# R203D.net
KiCad netlist of a schematic drawn in EAGLE
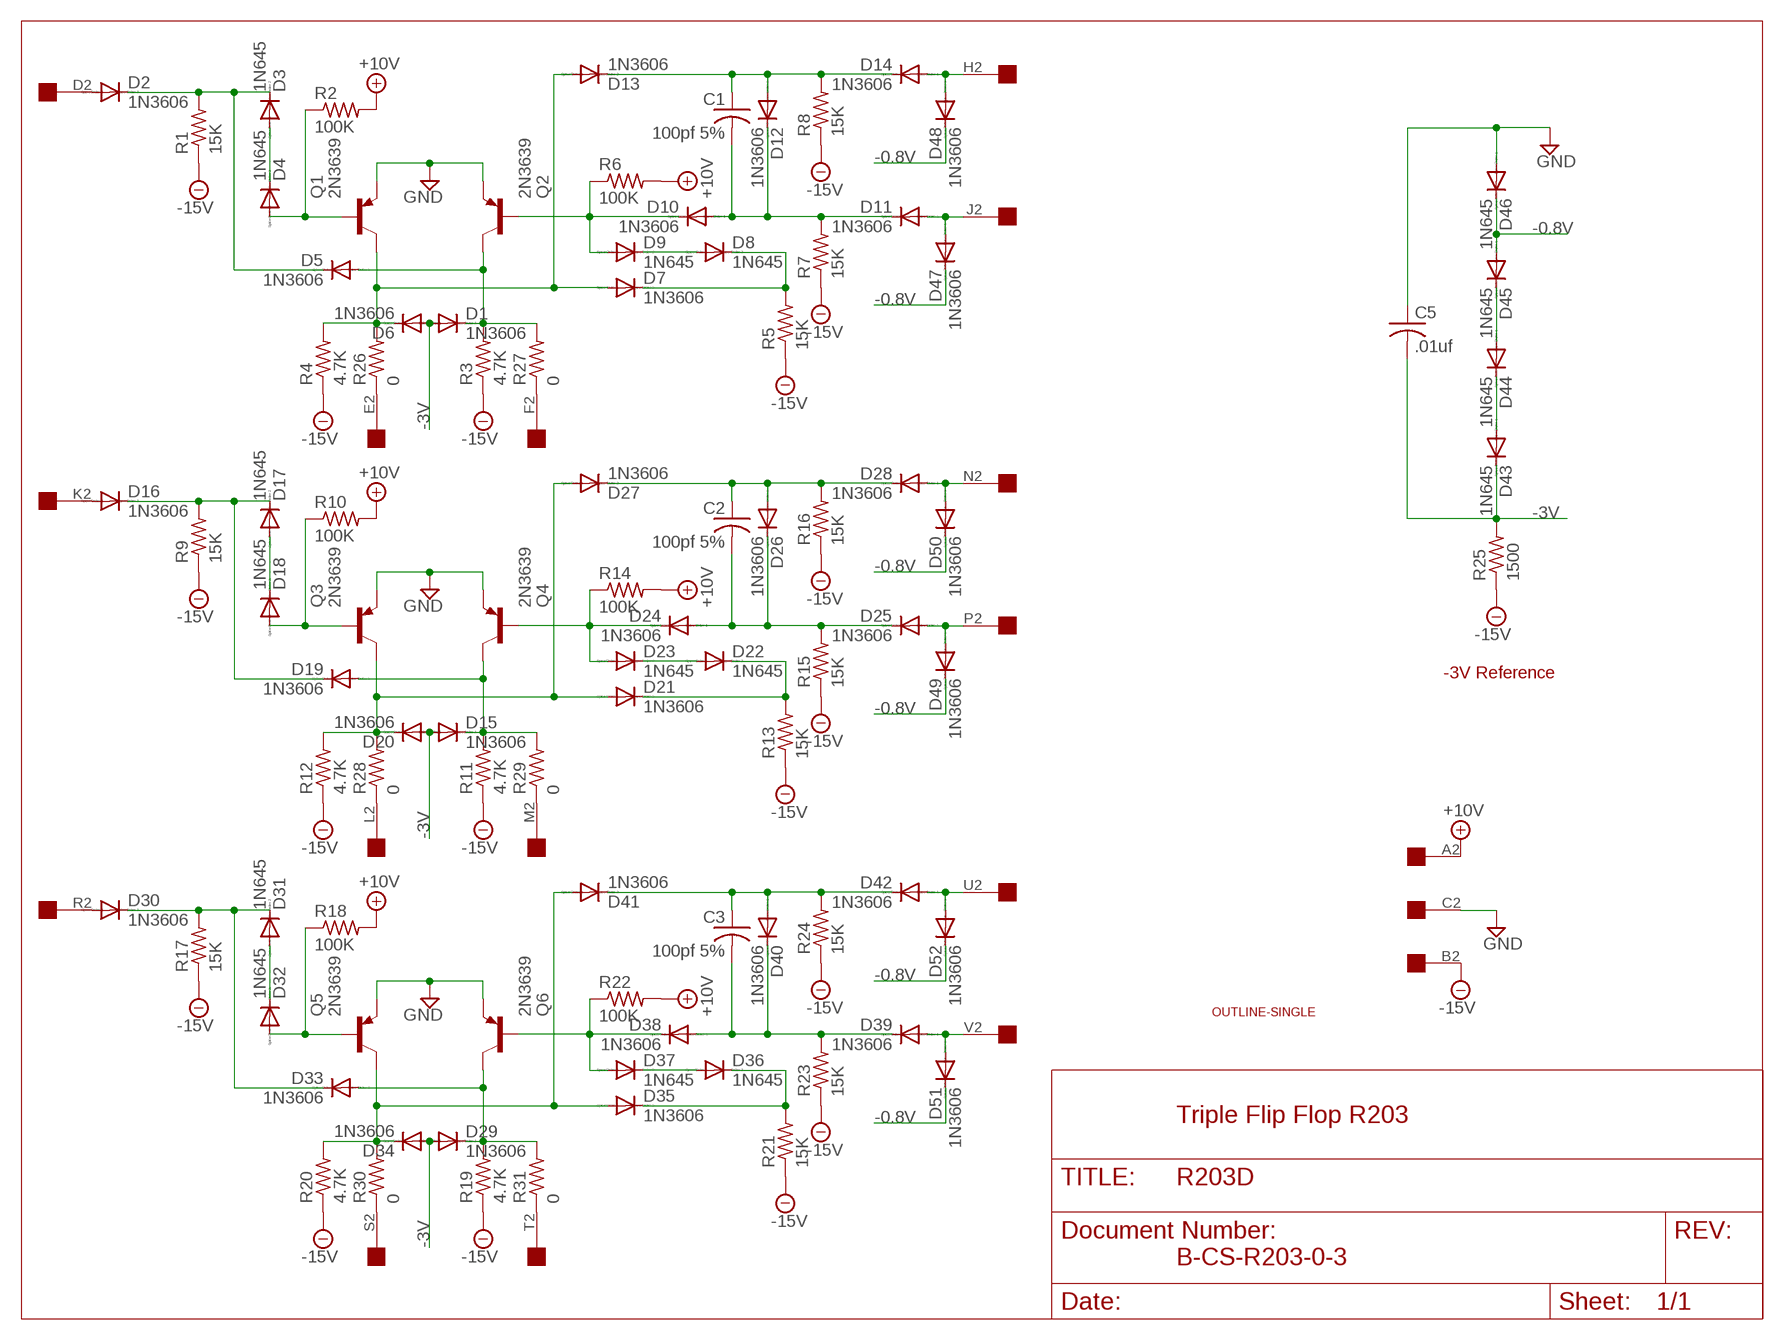
[diagram p0: schematic, sheet 1]

(export (version "E")
  (design (tool "Eeschema 10.0.6"))
  (components
    (comp (ref "C1")
      (value "100pf 5%")
      (footprint "eagle-import:C050-025X075")
      (libsource (lib "eagle-import") (part "C-US050-025X075"))
    )
    (comp (ref "C2")
      (value "100pf 5%")
      (footprint "eagle-import:C050-025X075")
      (libsource (lib "eagle-import") (part "C-US050-025X075"))
    )
    (comp (ref "C3")
      (value "100pf 5%")
      (footprint "eagle-import:C050-025X075")
      (libsource (lib "eagle-import") (part "C-US050-025X075"))
    )
    (comp (ref "C5")
      (value ".01uf")
      (footprint "eagle-import:C050-025X075")
      (libsource (lib "eagle-import") (part "C-US050-025X075"))
    )
    (comp (ref "D1")
      (value "1N3606")
      (footprint "eagle-import:DO35-10")
      (libsource (lib "eagle-import") (part "1N4148DO35-10"))
    )
    (comp (ref "D2")
      (value "1N3606")
      (footprint "eagle-import:DO35-10")
      (libsource (lib "eagle-import") (part "1N4148DO35-10"))
    )
    (comp (ref "D3")
      (value "1N645")
      (footprint "eagle-import:DO35-10")
      (libsource (lib "eagle-import") (part "1N4148DO35-10"))
    )
    (comp (ref "D4")
      (value "1N645")
      (footprint "eagle-import:DO35-10")
      (libsource (lib "eagle-import") (part "1N4148DO35-10"))
    )
    (comp (ref "D5")
      (value "1N3606")
      (footprint "eagle-import:DO35-10")
      (libsource (lib "eagle-import") (part "1N4148DO35-10"))
    )
    (comp (ref "D6")
      (value "1N3606")
      (footprint "eagle-import:DO35-10")
      (libsource (lib "eagle-import") (part "1N4148DO35-10"))
    )
    (comp (ref "D7")
      (value "1N3606")
      (footprint "eagle-import:DO35-10")
      (libsource (lib "eagle-import") (part "1N4148DO35-10"))
    )
    (comp (ref "D8")
      (value "1N645")
      (footprint "eagle-import:DO35-10")
      (libsource (lib "eagle-import") (part "1N4148DO35-10"))
    )
    (comp (ref "D9")
      (value "1N645")
      (footprint "eagle-import:DO35-10")
      (libsource (lib "eagle-import") (part "1N4148DO35-10"))
    )
    (comp (ref "D10")
      (value "1N3606")
      (footprint "eagle-import:DO35-10")
      (libsource (lib "eagle-import") (part "1N4148DO35-10"))
    )
    (comp (ref "D11")
      (value "1N3606")
      (footprint "eagle-import:DO35-10")
      (libsource (lib "eagle-import") (part "1N4148DO35-10"))
    )
    (comp (ref "D12")
      (value "1N3606")
      (footprint "eagle-import:DO35-10")
      (libsource (lib "eagle-import") (part "1N4148DO35-10"))
    )
    (comp (ref "D13")
      (value "1N3606")
      (footprint "eagle-import:DO35-10")
      (libsource (lib "eagle-import") (part "1N4148DO35-10"))
    )
    (comp (ref "D14")
      (value "1N3606")
      (footprint "eagle-import:DO35-10")
      (libsource (lib "eagle-import") (part "1N4148DO35-10"))
    )
    (comp (ref "D15")
      (value "1N3606")
      (footprint "eagle-import:DO35-10")
      (libsource (lib "eagle-import") (part "1N4148DO35-10"))
    )
    (comp (ref "D16")
      (value "1N3606")
      (footprint "eagle-import:DO35-10")
      (libsource (lib "eagle-import") (part "1N4148DO35-10"))
    )
    (comp (ref "D17")
      (value "1N645")
      (footprint "eagle-import:DO35-10")
      (libsource (lib "eagle-import") (part "1N4148DO35-10"))
    )
    (comp (ref "D18")
      (value "1N645")
      (footprint "eagle-import:DO35-10")
      (libsource (lib "eagle-import") (part "1N4148DO35-10"))
    )
    (comp (ref "D19")
      (value "1N3606")
      (footprint "eagle-import:DO35-10")
      (libsource (lib "eagle-import") (part "1N4148DO35-10"))
    )
    (comp (ref "D20")
      (value "1N3606")
      (footprint "eagle-import:DO35-10")
      (libsource (lib "eagle-import") (part "1N4148DO35-10"))
    )
    (comp (ref "D21")
      (value "1N3606")
      (footprint "eagle-import:DO35-10")
      (libsource (lib "eagle-import") (part "1N4148DO35-10"))
    )
    (comp (ref "D22")
      (value "1N645")
      (footprint "eagle-import:DO35-10")
      (libsource (lib "eagle-import") (part "1N4148DO35-10"))
    )
    (comp (ref "D23")
      (value "1N645")
      (footprint "eagle-import:DO35-10")
      (libsource (lib "eagle-import") (part "1N4148DO35-10"))
    )
    (comp (ref "D24")
      (value "1N3606")
      (footprint "eagle-import:DO35-10")
      (libsource (lib "eagle-import") (part "1N4148DO35-10"))
    )
    (comp (ref "D25")
      (value "1N3606")
      (footprint "eagle-import:DO35-10")
      (libsource (lib "eagle-import") (part "1N4148DO35-10"))
    )
    (comp (ref "D26")
      (value "1N3606")
      (footprint "eagle-import:DO35-10")
      (libsource (lib "eagle-import") (part "1N4148DO35-10"))
    )
    (comp (ref "D27")
      (value "1N3606")
      (footprint "eagle-import:DO35-10")
      (libsource (lib "eagle-import") (part "1N4148DO35-10"))
    )
    (comp (ref "D28")
      (value "1N3606")
      (footprint "eagle-import:DO35-10")
      (libsource (lib "eagle-import") (part "1N4148DO35-10"))
    )
    (comp (ref "D29")
      (value "1N3606")
      (footprint "eagle-import:DO35-10")
      (libsource (lib "eagle-import") (part "1N4148DO35-10"))
    )
    (comp (ref "D30")
      (value "1N3606")
      (footprint "eagle-import:DO35-10")
      (libsource (lib "eagle-import") (part "1N4148DO35-10"))
    )
    (comp (ref "D31")
      (value "1N645")
      (footprint "eagle-import:DO35-10")
      (libsource (lib "eagle-import") (part "1N4148DO35-10"))
    )
    (comp (ref "D32")
      (value "1N645")
      (footprint "eagle-import:DO35-10")
      (libsource (lib "eagle-import") (part "1N4148DO35-10"))
    )
    (comp (ref "D33")
      (value "1N3606")
      (footprint "eagle-import:DO35-10")
      (libsource (lib "eagle-import") (part "1N4148DO35-10"))
    )
    (comp (ref "D34")
      (value "1N3606")
      (footprint "eagle-import:DO35-10")
      (libsource (lib "eagle-import") (part "1N4148DO35-10"))
    )
    (comp (ref "D35")
      (value "1N3606")
      (footprint "eagle-import:DO35-10")
      (libsource (lib "eagle-import") (part "1N4148DO35-10"))
    )
    (comp (ref "D36")
      (value "1N645")
      (footprint "eagle-import:DO35-10")
      (libsource (lib "eagle-import") (part "1N4148DO35-10"))
    )
    (comp (ref "D37")
      (value "1N645")
      (footprint "eagle-import:DO35-10")
      (libsource (lib "eagle-import") (part "1N4148DO35-10"))
    )
    (comp (ref "D38")
      (value "1N3606")
      (footprint "eagle-import:DO35-10")
      (libsource (lib "eagle-import") (part "1N4148DO35-10"))
    )
    (comp (ref "D39")
      (value "1N3606")
      (footprint "eagle-import:DO35-10")
      (libsource (lib "eagle-import") (part "1N4148DO35-10"))
    )
    (comp (ref "D40")
      (value "1N3606")
      (footprint "eagle-import:DO35-10")
      (libsource (lib "eagle-import") (part "1N4148DO35-10"))
    )
    (comp (ref "D41")
      (value "1N3606")
      (footprint "eagle-import:DO35-10")
      (libsource (lib "eagle-import") (part "1N4148DO35-10"))
    )
    (comp (ref "D42")
      (value "1N3606")
      (footprint "eagle-import:DO35-10")
      (libsource (lib "eagle-import") (part "1N4148DO35-10"))
    )
    (comp (ref "D43")
      (value "1N645")
      (footprint "eagle-import:DO35-10")
      (libsource (lib "eagle-import") (part "1N4148DO35-10"))
    )
    (comp (ref "D44")
      (value "1N645")
      (footprint "eagle-import:DO35-10")
      (libsource (lib "eagle-import") (part "1N4148DO35-10"))
    )
    (comp (ref "D45")
      (value "1N645")
      (footprint "eagle-import:DO35-10")
      (libsource (lib "eagle-import") (part "1N4148DO35-10"))
    )
    (comp (ref "D46")
      (value "1N645")
      (footprint "eagle-import:DO35-10")
      (libsource (lib "eagle-import") (part "1N4148DO35-10"))
    )
    (comp (ref "D47")
      (value "1N3606")
      (footprint "eagle-import:DO35-10")
      (libsource (lib "eagle-import") (part "1N4148DO35-10"))
    )
    (comp (ref "D48")
      (value "1N3606")
      (footprint "eagle-import:DO35-10")
      (libsource (lib "eagle-import") (part "1N4148DO35-10"))
    )
    (comp (ref "D49")
      (value "1N3606")
      (footprint "eagle-import:DO35-10")
      (libsource (lib "eagle-import") (part "1N4148DO35-10"))
    )
    (comp (ref "D50")
      (value "1N3606")
      (footprint "eagle-import:DO35-10")
      (libsource (lib "eagle-import") (part "1N4148DO35-10"))
    )
    (comp (ref "D51")
      (value "1N3606")
      (footprint "eagle-import:DO35-10")
      (libsource (lib "eagle-import") (part "1N4148DO35-10"))
    )
    (comp (ref "D52")
      (value "1N3606")
      (footprint "eagle-import:DO35-10")
      (libsource (lib "eagle-import") (part "1N4148DO35-10"))
    )
    (comp (ref "Q1")
      (value "2N3639")
      (footprint "eagle-import:TO39")
      (libsource (lib "eagle-import") (part "2N3637"))
    )
    (comp (ref "Q2")
      (value "2N3639")
      (footprint "eagle-import:TO39")
      (libsource (lib "eagle-import") (part "2N3637"))
    )
    (comp (ref "Q3")
      (value "2N3639")
      (footprint "eagle-import:TO39")
      (libsource (lib "eagle-import") (part "2N3637"))
    )
    (comp (ref "Q4")
      (value "2N3639")
      (footprint "eagle-import:TO39")
      (libsource (lib "eagle-import") (part "2N3637"))
    )
    (comp (ref "Q5")
      (value "2N3639")
      (footprint "eagle-import:TO39")
      (libsource (lib "eagle-import") (part "2N3637"))
    )
    (comp (ref "Q6")
      (value "2N3639")
      (footprint "eagle-import:TO39")
      (libsource (lib "eagle-import") (part "2N3637"))
    )
    (comp (ref "R1")
      (value "15K")
      (footprint "eagle-import:0207_10")
      (libsource (lib "eagle-import") (part "R-US_0207/10"))
    )
    (comp (ref "R2")
      (value "100K")
      (footprint "eagle-import:0207_10")
      (libsource (lib "eagle-import") (part "R-US_0207/10"))
    )
    (comp (ref "R3")
      (value "4.7K")
      (footprint "eagle-import:0207_10")
      (libsource (lib "eagle-import") (part "R-US_0207/10"))
    )
    (comp (ref "R4")
      (value "4.7K")
      (footprint "eagle-import:0207_10")
      (libsource (lib "eagle-import") (part "R-US_0207/10"))
    )
    (comp (ref "R5")
      (value "15K")
      (footprint "eagle-import:0207_10")
      (libsource (lib "eagle-import") (part "R-US_0207/10"))
    )
    (comp (ref "R6")
      (value "100K")
      (footprint "eagle-import:0207_10")
      (libsource (lib "eagle-import") (part "R-US_0207/10"))
    )
    (comp (ref "R7")
      (value "15K")
      (footprint "eagle-import:0207_10")
      (libsource (lib "eagle-import") (part "R-US_0207/10"))
    )
    (comp (ref "R8")
      (value "15K")
      (footprint "eagle-import:0207_10")
      (libsource (lib "eagle-import") (part "R-US_0207/10"))
    )
    (comp (ref "R9")
      (value "15K")
      (footprint "eagle-import:0207_10")
      (libsource (lib "eagle-import") (part "R-US_0207/10"))
    )
    (comp (ref "R10")
      (value "100K")
      (footprint "eagle-import:0207_10")
      (libsource (lib "eagle-import") (part "R-US_0207/10"))
    )
    (comp (ref "R11")
      (value "4.7K")
      (footprint "eagle-import:0207_10")
      (libsource (lib "eagle-import") (part "R-US_0207/10"))
    )
    (comp (ref "R12")
      (value "4.7K")
      (footprint "eagle-import:0207_10")
      (libsource (lib "eagle-import") (part "R-US_0207/10"))
    )
    (comp (ref "R13")
      (value "15K")
      (footprint "eagle-import:0207_10")
      (libsource (lib "eagle-import") (part "R-US_0207/10"))
    )
    (comp (ref "R14")
      (value "100K")
      (footprint "eagle-import:0207_10")
      (libsource (lib "eagle-import") (part "R-US_0207/10"))
    )
    (comp (ref "R15")
      (value "15K")
      (footprint "eagle-import:0207_10")
      (libsource (lib "eagle-import") (part "R-US_0207/10"))
    )
    (comp (ref "R16")
      (value "15K")
      (footprint "eagle-import:0207_10")
      (libsource (lib "eagle-import") (part "R-US_0207/10"))
    )
    (comp (ref "R17")
      (value "15K")
      (footprint "eagle-import:0207_10")
      (libsource (lib "eagle-import") (part "R-US_0207/10"))
    )
    (comp (ref "R18")
      (value "100K")
      (footprint "eagle-import:0207_10")
      (libsource (lib "eagle-import") (part "R-US_0207/10"))
    )
    (comp (ref "R19")
      (value "4.7K")
      (footprint "eagle-import:0207_10")
      (libsource (lib "eagle-import") (part "R-US_0207/10"))
    )
    (comp (ref "R20")
      (value "4.7K")
      (footprint "eagle-import:0207_10")
      (libsource (lib "eagle-import") (part "R-US_0207/10"))
    )
    (comp (ref "R21")
      (value "15K")
      (footprint "eagle-import:0207_10")
      (libsource (lib "eagle-import") (part "R-US_0207/10"))
    )
    (comp (ref "R22")
      (value "100K")
      (footprint "eagle-import:0207_10")
      (libsource (lib "eagle-import") (part "R-US_0207/10"))
    )
    (comp (ref "R23")
      (value "15K")
      (footprint "eagle-import:0207_10")
      (libsource (lib "eagle-import") (part "R-US_0207/10"))
    )
    (comp (ref "R24")
      (value "15K")
      (footprint "eagle-import:0207_10")
      (libsource (lib "eagle-import") (part "R-US_0207/10"))
    )
    (comp (ref "R25")
      (value "1500")
      (footprint "eagle-import:0207_10")
      (libsource (lib "eagle-import") (part "R-US_0207/10"))
    )
    (comp (ref "R26")
      (value "0")
      (footprint "eagle-import:0207_10")
      (libsource (lib "eagle-import") (part "R-US_0207/10"))
    )
    (comp (ref "R27")
      (value "0")
      (footprint "eagle-import:0207_10")
      (libsource (lib "eagle-import") (part "R-US_0207/10"))
    )
    (comp (ref "R28")
      (value "0")
      (footprint "eagle-import:0207_10")
      (libsource (lib "eagle-import") (part "R-US_0207/10"))
    )
    (comp (ref "R29")
      (value "0")
      (footprint "eagle-import:0207_10")
      (libsource (lib "eagle-import") (part "R-US_0207/10"))
    )
    (comp (ref "R30")
      (value "0")
      (footprint "eagle-import:0207_10")
      (libsource (lib "eagle-import") (part "R-US_0207/10"))
    )
    (comp (ref "R31")
      (value "0")
      (footprint "eagle-import:0207_10")
      (libsource (lib "eagle-import") (part "R-US_0207/10"))
    )
    (comp (ref "U$1")
      (value "OUTLINE-SINGLE")
      (footprint "eagle-import:SINGLE")
      (libsource (lib "eagle-import") (part "OUTLINE-SINGLE"))
    )
    (comp (ref "U$2")
      (value "EDGE-1")
      (footprint "eagle-import:EDGE-CON1")
      (libsource (lib "eagle-import") (part "EDGE-1"))
    )
  )
  (nets
    (net (code "1") (name "+10V") (class "Default")
      (node (ref "R10") (pin "2") (pinfunction "2_2") (pintype "passive"))
      (node (ref "R14") (pin "2") (pinfunction "2_2") (pintype "passive"))
      (node (ref "R18") (pin "2") (pinfunction "2_2") (pintype "passive"))
      (node (ref "R2") (pin "2") (pinfunction "2_2") (pintype "passive"))
      (node (ref "R22") (pin "2") (pinfunction "2_2") (pintype "passive"))
      (node (ref "R6") (pin "2") (pinfunction "2_2") (pintype "passive"))
      (node (ref "U$2") (pin "A2") (pinfunction "1_A2") (pintype "bidirectional"))
    )
    (net (code "2") (name "-15V") (class "Default")
      (node (ref "R1") (pin "1") (pinfunction "1_1") (pintype "passive"))
      (node (ref "R11") (pin "1") (pinfunction "1_1") (pintype "passive"))
      (node (ref "R12") (pin "1") (pinfunction "1_1") (pintype "passive"))
      (node (ref "R13") (pin "1") (pinfunction "1_1") (pintype "passive"))
      (node (ref "R15") (pin "1") (pinfunction "1_1") (pintype "passive"))
      (node (ref "R16") (pin "1") (pinfunction "1_1") (pintype "passive"))
      (node (ref "R17") (pin "1") (pinfunction "1_1") (pintype "passive"))
      (node (ref "R19") (pin "1") (pinfunction "1_1") (pintype "passive"))
      (node (ref "R20") (pin "1") (pinfunction "1_1") (pintype "passive"))
      (node (ref "R21") (pin "1") (pinfunction "1_1") (pintype "passive"))
      (node (ref "R23") (pin "1") (pinfunction "1_1") (pintype "passive"))
      (node (ref "R24") (pin "1") (pinfunction "1_1") (pintype "passive"))
      (node (ref "R25") (pin "1") (pinfunction "1_1") (pintype "passive"))
      (node (ref "R3") (pin "1") (pinfunction "1_1") (pintype "passive"))
      (node (ref "R4") (pin "1") (pinfunction "1_1") (pintype "passive"))
      (node (ref "R5") (pin "1") (pinfunction "1_1") (pintype "passive"))
      (node (ref "R7") (pin "1") (pinfunction "1_1") (pintype "passive"))
      (node (ref "R8") (pin "1") (pinfunction "1_1") (pintype "passive"))
      (node (ref "R9") (pin "1") (pinfunction "1_1") (pintype "passive"))
      (node (ref "U$2") (pin "B2") (pinfunction "1_B2") (pintype "bidirectional"))
    )
    (net (code "3") (name "/-0.8V") (class "Default")
      (node (ref "D45") (pin "A") (pinfunction "A_A") (pintype "passive"))
      (node (ref "D46") (pin "C") (pinfunction "C_C") (pintype "passive"))
      (node (ref "D47") (pin "C") (pinfunction "C_C") (pintype "passive"))
      (node (ref "D48") (pin "C") (pinfunction "C_C") (pintype "passive"))
      (node (ref "D49") (pin "C") (pinfunction "C_C") (pintype "passive"))
      (node (ref "D50") (pin "C") (pinfunction "C_C") (pintype "passive"))
      (node (ref "D51") (pin "C") (pinfunction "C_C") (pintype "passive"))
      (node (ref "D52") (pin "C") (pinfunction "C_C") (pintype "passive"))
    )
    (net (code "4") (name "/-3V") (class "Default")
      (node (ref "C5") (pin "2") (pinfunction "2_2") (pintype "passive"))
      (node (ref "D1") (pin "A") (pinfunction "A_A") (pintype "passive"))
      (node (ref "D15") (pin "A") (pinfunction "A_A") (pintype "passive"))
      (node (ref "D20") (pin "A") (pinfunction "A_A") (pintype "passive"))
      (node (ref "D29") (pin "A") (pinfunction "A_A") (pintype "passive"))
      (node (ref "D34") (pin "A") (pinfunction "A_A") (pintype "passive"))
      (node (ref "D43") (pin "C") (pinfunction "C_C") (pintype "passive"))
      (node (ref "D6") (pin "A") (pinfunction "A_A") (pintype "passive"))
      (node (ref "R25") (pin "2") (pinfunction "2_2") (pintype "passive"))
    )
    (net (code "5") (name "GND") (class "Default")
      (node (ref "C5") (pin "1") (pinfunction "1_1") (pintype "passive"))
      (node (ref "D46") (pin "A") (pinfunction "A_A") (pintype "passive"))
      (node (ref "Q1") (pin "1") (pinfunction "E_1") (pintype "passive"))
      (node (ref "Q2") (pin "1") (pinfunction "E_1") (pintype "passive"))
      (node (ref "Q3") (pin "1") (pinfunction "E_1") (pintype "passive"))
      (node (ref "Q4") (pin "1") (pinfunction "E_1") (pintype "passive"))
      (node (ref "Q5") (pin "1") (pinfunction "E_1") (pintype "passive"))
      (node (ref "Q6") (pin "1") (pinfunction "E_1") (pintype "passive"))
      (node (ref "U$2") (pin "C2") (pinfunction "1_C2") (pintype "bidirectional"))
    )
    (net (code "6") (name "Net-(C1-Pad1)") (class "Default")
      (node (ref "C1") (pin "1") (pinfunction "1_1") (pintype "passive"))
      (node (ref "D12") (pin "A") (pinfunction "A_A") (pintype "passive"))
      (node (ref "D13") (pin "C") (pinfunction "C_C") (pintype "passive"))
      (node (ref "D14") (pin "C") (pinfunction "C_C") (pintype "passive"))
      (node (ref "R8") (pin "2") (pinfunction "2_2") (pintype "passive"))
    )
    (net (code "7") (name "Net-(C1-Pad2)") (class "Default")
      (node (ref "C1") (pin "2") (pinfunction "2_2") (pintype "passive"))
      (node (ref "D10") (pin "A") (pinfunction "A_A") (pintype "passive"))
      (node (ref "D11") (pin "C") (pinfunction "C_C") (pintype "passive"))
      (node (ref "D12") (pin "C") (pinfunction "C_C") (pintype "passive"))
      (node (ref "R7") (pin "2") (pinfunction "2_2") (pintype "passive"))
    )
    (net (code "8") (name "Net-(C2-Pad1)") (class "Default")
      (node (ref "C2") (pin "1") (pinfunction "1_1") (pintype "passive"))
      (node (ref "D26") (pin "A") (pinfunction "A_A") (pintype "passive"))
      (node (ref "D27") (pin "C") (pinfunction "C_C") (pintype "passive"))
      (node (ref "D28") (pin "C") (pinfunction "C_C") (pintype "passive"))
      (node (ref "R16") (pin "2") (pinfunction "2_2") (pintype "passive"))
    )
    (net (code "9") (name "Net-(C2-Pad2)") (class "Default")
      (node (ref "C2") (pin "2") (pinfunction "2_2") (pintype "passive"))
      (node (ref "D24") (pin "A") (pinfunction "A_A") (pintype "passive"))
      (node (ref "D25") (pin "C") (pinfunction "C_C") (pintype "passive"))
      (node (ref "D26") (pin "C") (pinfunction "C_C") (pintype "passive"))
      (node (ref "R15") (pin "2") (pinfunction "2_2") (pintype "passive"))
    )
    (net (code "10") (name "Net-(C3-Pad1)") (class "Default")
      (node (ref "C3") (pin "1") (pinfunction "1_1") (pintype "passive"))
      (node (ref "D40") (pin "A") (pinfunction "A_A") (pintype "passive"))
      (node (ref "D41") (pin "C") (pinfunction "C_C") (pintype "passive"))
      (node (ref "D42") (pin "C") (pinfunction "C_C") (pintype "passive"))
      (node (ref "R24") (pin "2") (pinfunction "2_2") (pintype "passive"))
    )
    (net (code "11") (name "Net-(C3-Pad2)") (class "Default")
      (node (ref "C3") (pin "2") (pinfunction "2_2") (pintype "passive"))
      (node (ref "D38") (pin "A") (pinfunction "A_A") (pintype "passive"))
      (node (ref "D39") (pin "C") (pinfunction "C_C") (pintype "passive"))
      (node (ref "D40") (pin "C") (pinfunction "C_C") (pintype "passive"))
      (node (ref "R23") (pin "2") (pinfunction "2_2") (pintype "passive"))
    )
    (net (code "12") (name "Net-(D2-PadC)") (class "Default")
      (node (ref "D2") (pin "C") (pinfunction "C_C") (pintype "passive"))
      (node (ref "D3") (pin "C") (pinfunction "C_C") (pintype "passive"))
      (node (ref "D5") (pin "C") (pinfunction "C_C") (pintype "passive"))
      (node (ref "R1") (pin "2") (pinfunction "2_2") (pintype "passive"))
    )
    (net (code "13") (name "Net-(D3-PadA)") (class "Default")
      (node (ref "D3") (pin "A") (pinfunction "A_A") (pintype "passive"))
      (node (ref "D4") (pin "C") (pinfunction "C_C") (pintype "passive"))
    )
    (net (code "14") (name "Net-(D7-PadC)") (class "Default")
      (node (ref "D7") (pin "C") (pinfunction "C_C") (pintype "passive"))
      (node (ref "D8") (pin "C") (pinfunction "C_C") (pintype "passive"))
      (node (ref "R5") (pin "2") (pinfunction "2_2") (pintype "passive"))
    )
    (net (code "15") (name "Net-(D8-PadA)") (class "Default")
      (node (ref "D8") (pin "A") (pinfunction "A_A") (pintype "passive"))
      (node (ref "D9") (pin "C") (pinfunction "C_C") (pintype "passive"))
    )
    (net (code "16") (name "Net-(D16-PadC)") (class "Default")
      (node (ref "D16") (pin "C") (pinfunction "C_C") (pintype "passive"))
      (node (ref "D17") (pin "C") (pinfunction "C_C") (pintype "passive"))
      (node (ref "D19") (pin "C") (pinfunction "C_C") (pintype "passive"))
      (node (ref "R9") (pin "2") (pinfunction "2_2") (pintype "passive"))
    )
    (net (code "17") (name "Net-(D17-PadA)") (class "Default")
      (node (ref "D17") (pin "A") (pinfunction "A_A") (pintype "passive"))
      (node (ref "D18") (pin "C") (pinfunction "C_C") (pintype "passive"))
    )
    (net (code "18") (name "Net-(D21-PadC)") (class "Default")
      (node (ref "D21") (pin "C") (pinfunction "C_C") (pintype "passive"))
      (node (ref "D22") (pin "C") (pinfunction "C_C") (pintype "passive"))
      (node (ref "R13") (pin "2") (pinfunction "2_2") (pintype "passive"))
    )
    (net (code "19") (name "Net-(D22-PadA)") (class "Default")
      (node (ref "D22") (pin "A") (pinfunction "A_A") (pintype "passive"))
      (node (ref "D23") (pin "C") (pinfunction "C_C") (pintype "passive"))
    )
    (net (code "20") (name "Net-(D30-PadC)") (class "Default")
      (node (ref "D30") (pin "C") (pinfunction "C_C") (pintype "passive"))
      (node (ref "D31") (pin "C") (pinfunction "C_C") (pintype "passive"))
      (node (ref "D33") (pin "C") (pinfunction "C_C") (pintype "passive"))
      (node (ref "R17") (pin "2") (pinfunction "2_2") (pintype "passive"))
    )
    (net (code "21") (name "Net-(D31-PadA)") (class "Default")
      (node (ref "D31") (pin "A") (pinfunction "A_A") (pintype "passive"))
      (node (ref "D32") (pin "C") (pinfunction "C_C") (pintype "passive"))
    )
    (net (code "22") (name "Net-(D35-PadC)") (class "Default")
      (node (ref "D35") (pin "C") (pinfunction "C_C") (pintype "passive"))
      (node (ref "D36") (pin "C") (pinfunction "C_C") (pintype "passive"))
      (node (ref "R21") (pin "2") (pinfunction "2_2") (pintype "passive"))
    )
    (net (code "23") (name "Net-(D36-PadA)") (class "Default")
      (node (ref "D36") (pin "A") (pinfunction "A_A") (pintype "passive"))
      (node (ref "D37") (pin "C") (pinfunction "C_C") (pintype "passive"))
    )
    (net (code "24") (name "Net-(D43-PadA)") (class "Default")
      (node (ref "D43") (pin "A") (pinfunction "A_A") (pintype "passive"))
      (node (ref "D44") (pin "C") (pinfunction "C_C") (pintype "passive"))
    )
    (net (code "25") (name "Net-(D44-PadA)") (class "Default")
      (node (ref "D44") (pin "A") (pinfunction "A_A") (pintype "passive"))
      (node (ref "D45") (pin "C") (pinfunction "C_C") (pintype "passive"))
    )
    (net (code "26") (name "Net-(Q1-B)") (class "Default")
      (node (ref "D4") (pin "A") (pinfunction "A_A") (pintype "passive"))
      (node (ref "Q1") (pin "2") (pinfunction "B_2") (pintype "passive"))
      (node (ref "R2") (pin "1") (pinfunction "1_1") (pintype "passive"))
    )
    (net (code "27") (name "Net-(Q1-C)") (class "Default")
      (node (ref "D13") (pin "A") (pinfunction "A_A") (pintype "passive"))
      (node (ref "D6") (pin "C") (pinfunction "C_C") (pintype "passive"))
      (node (ref "D7") (pin "A") (pinfunction "A_A") (pintype "passive"))
      (node (ref "Q1") (pin "3") (pinfunction "C_3") (pintype "passive"))
      (node (ref "R26") (pin "2") (pinfunction "2_2") (pintype "passive"))
      (node (ref "R4") (pin "2") (pinfunction "2_2") (pintype "passive"))
    )
    (net (code "28") (name "Net-(Q2-B)") (class "Default")
      (node (ref "D10") (pin "C") (pinfunction "C_C") (pintype "passive"))
      (node (ref "D9") (pin "A") (pinfunction "A_A") (pintype "passive"))
      (node (ref "Q2") (pin "2") (pinfunction "B_2") (pintype "passive"))
      (node (ref "R6") (pin "1") (pinfunction "1_1") (pintype "passive"))
    )
    (net (code "29") (name "Net-(Q2-C)") (class "Default")
      (node (ref "D1") (pin "C") (pinfunction "C_C") (pintype "passive"))
      (node (ref "D5") (pin "A") (pinfunction "A_A") (pintype "passive"))
      (node (ref "Q2") (pin "3") (pinfunction "C_3") (pintype "passive"))
      (node (ref "R27") (pin "2") (pinfunction "2_2") (pintype "passive"))
      (node (ref "R3") (pin "2") (pinfunction "2_2") (pintype "passive"))
    )
    (net (code "30") (name "Net-(Q3-B)") (class "Default")
      (node (ref "D18") (pin "A") (pinfunction "A_A") (pintype "passive"))
      (node (ref "Q3") (pin "2") (pinfunction "B_2") (pintype "passive"))
      (node (ref "R10") (pin "1") (pinfunction "1_1") (pintype "passive"))
    )
    (net (code "31") (name "Net-(Q3-C)") (class "Default")
      (node (ref "D20") (pin "C") (pinfunction "C_C") (pintype "passive"))
      (node (ref "D21") (pin "A") (pinfunction "A_A") (pintype "passive"))
      (node (ref "D27") (pin "A") (pinfunction "A_A") (pintype "passive"))
      (node (ref "Q3") (pin "3") (pinfunction "C_3") (pintype "passive"))
      (node (ref "R12") (pin "2") (pinfunction "2_2") (pintype "passive"))
      (node (ref "R28") (pin "2") (pinfunction "2_2") (pintype "passive"))
    )
    (net (code "32") (name "Net-(Q4-B)") (class "Default")
      (node (ref "D23") (pin "A") (pinfunction "A_A") (pintype "passive"))
      (node (ref "D24") (pin "C") (pinfunction "C_C") (pintype "passive"))
      (node (ref "Q4") (pin "2") (pinfunction "B_2") (pintype "passive"))
      (node (ref "R14") (pin "1") (pinfunction "1_1") (pintype "passive"))
    )
    (net (code "33") (name "Net-(Q4-C)") (class "Default")
      (node (ref "D15") (pin "C") (pinfunction "C_C") (pintype "passive"))
      (node (ref "D19") (pin "A") (pinfunction "A_A") (pintype "passive"))
      (node (ref "Q4") (pin "3") (pinfunction "C_3") (pintype "passive"))
      (node (ref "R11") (pin "2") (pinfunction "2_2") (pintype "passive"))
      (node (ref "R29") (pin "2") (pinfunction "2_2") (pintype "passive"))
    )
    (net (code "34") (name "Net-(Q5-B)") (class "Default")
      (node (ref "D32") (pin "A") (pinfunction "A_A") (pintype "passive"))
      (node (ref "Q5") (pin "2") (pinfunction "B_2") (pintype "passive"))
      (node (ref "R18") (pin "1") (pinfunction "1_1") (pintype "passive"))
    )
    (net (code "35") (name "Net-(Q5-C)") (class "Default")
      (node (ref "D34") (pin "C") (pinfunction "C_C") (pintype "passive"))
      (node (ref "D35") (pin "A") (pinfunction "A_A") (pintype "passive"))
      (node (ref "D41") (pin "A") (pinfunction "A_A") (pintype "passive"))
      (node (ref "Q5") (pin "3") (pinfunction "C_3") (pintype "passive"))
      (node (ref "R20") (pin "2") (pinfunction "2_2") (pintype "passive"))
      (node (ref "R30") (pin "2") (pinfunction "2_2") (pintype "passive"))
    )
    (net (code "36") (name "Net-(Q6-B)") (class "Default")
      (node (ref "D37") (pin "A") (pinfunction "A_A") (pintype "passive"))
      (node (ref "D38") (pin "C") (pinfunction "C_C") (pintype "passive"))
      (node (ref "Q6") (pin "2") (pinfunction "B_2") (pintype "passive"))
      (node (ref "R22") (pin "1") (pinfunction "1_1") (pintype "passive"))
    )
    (net (code "37") (name "Net-(Q6-C)") (class "Default")
      (node (ref "D29") (pin "C") (pinfunction "C_C") (pintype "passive"))
      (node (ref "D33") (pin "A") (pinfunction "A_A") (pintype "passive"))
      (node (ref "Q6") (pin "3") (pinfunction "C_3") (pintype "passive"))
      (node (ref "R19") (pin "2") (pinfunction "2_2") (pintype "passive"))
      (node (ref "R31") (pin "2") (pinfunction "2_2") (pintype "passive"))
    )
    (net (code "38") (name "Net-(U$2D-1)") (class "Default")
      (node (ref "D2") (pin "A") (pinfunction "A_A") (pintype "passive"))
      (node (ref "U$2") (pin "D2") (pinfunction "1_D2") (pintype "bidirectional"))
    )
    (net (code "39") (name "Net-(U$2E-1)") (class "Default")
      (node (ref "R26") (pin "1") (pinfunction "1_1") (pintype "passive"))
      (node (ref "U$2") (pin "E2") (pinfunction "1_E2") (pintype "bidirectional"))
    )
    (net (code "40") (name "Net-(U$2F-1)") (class "Default")
      (node (ref "R27") (pin "1") (pinfunction "1_1") (pintype "passive"))
      (node (ref "U$2") (pin "F2") (pinfunction "1_F2") (pintype "bidirectional"))
    )
    (net (code "41") (name "Net-(U$2G-1)") (class "Default")
      (node (ref "D14") (pin "A") (pinfunction "A_A") (pintype "passive"))
      (node (ref "D48") (pin "A") (pinfunction "A_A") (pintype "passive"))
      (node (ref "U$2") (pin "H2") (pinfunction "1_H2") (pintype "bidirectional"))
    )
    (net (code "42") (name "Net-(U$2H-1)") (class "Default")
      (node (ref "D11") (pin "A") (pinfunction "A_A") (pintype "passive"))
      (node (ref "D47") (pin "A") (pinfunction "A_A") (pintype "passive"))
      (node (ref "U$2") (pin "J2") (pinfunction "1_J2") (pintype "bidirectional"))
    )
    (net (code "43") (name "Net-(U$2I-1)") (class "Default")
      (node (ref "D16") (pin "A") (pinfunction "A_A") (pintype "passive"))
      (node (ref "U$2") (pin "K2") (pinfunction "1_K2") (pintype "bidirectional"))
    )
    (net (code "44") (name "Net-(U$2J-1)") (class "Default")
      (node (ref "R28") (pin "1") (pinfunction "1_1") (pintype "passive"))
      (node (ref "U$2") (pin "L2") (pinfunction "1_L2") (pintype "bidirectional"))
    )
    (net (code "45") (name "Net-(U$2K-1)") (class "Default")
      (node (ref "R29") (pin "1") (pinfunction "1_1") (pintype "passive"))
      (node (ref "U$2") (pin "M2") (pinfunction "1_M2") (pintype "bidirectional"))
    )
    (net (code "46") (name "Net-(U$2L-1)") (class "Default")
      (node (ref "D28") (pin "A") (pinfunction "A_A") (pintype "passive"))
      (node (ref "D50") (pin "A") (pinfunction "A_A") (pintype "passive"))
      (node (ref "U$2") (pin "N2") (pinfunction "1_N2") (pintype "bidirectional"))
    )
    (net (code "47") (name "Net-(U$2M-1)") (class "Default")
      (node (ref "D25") (pin "A") (pinfunction "A_A") (pintype "passive"))
      (node (ref "D49") (pin "A") (pinfunction "A_A") (pintype "passive"))
      (node (ref "U$2") (pin "P2") (pinfunction "1_P2") (pintype "bidirectional"))
    )
    (net (code "48") (name "Net-(U$2N-1)") (class "Default")
      (node (ref "D30") (pin "A") (pinfunction "A_A") (pintype "passive"))
      (node (ref "U$2") (pin "R2") (pinfunction "1_R2") (pintype "bidirectional"))
    )
    (net (code "49") (name "Net-(U$2O-1)") (class "Default")
      (node (ref "R30") (pin "1") (pinfunction "1_1") (pintype "passive"))
      (node (ref "U$2") (pin "S2") (pinfunction "1_S2") (pintype "bidirectional"))
    )
    (net (code "50") (name "Net-(U$2P-1)") (class "Default")
      (node (ref "R31") (pin "1") (pinfunction "1_1") (pintype "passive"))
      (node (ref "U$2") (pin "T2") (pinfunction "1_T2") (pintype "bidirectional"))
    )
    (net (code "51") (name "Net-(U$2Q-1)") (class "Default")
      (node (ref "D42") (pin "A") (pinfunction "A_A") (pintype "passive"))
      (node (ref "D52") (pin "A") (pinfunction "A_A") (pintype "passive"))
      (node (ref "U$2") (pin "U2") (pinfunction "1_U2") (pintype "bidirectional"))
    )
    (net (code "52") (name "Net-(U$2R-1)") (class "Default")
      (node (ref "D39") (pin "A") (pinfunction "A_A") (pintype "passive"))
      (node (ref "D51") (pin "A") (pinfunction "A_A") (pintype "passive"))
      (node (ref "U$2") (pin "V2") (pinfunction "1_V2") (pintype "bidirectional"))
    )
  )
)
